# MYO_connector_2.net
KiCad netlist of a schematic drawn in EAGLE
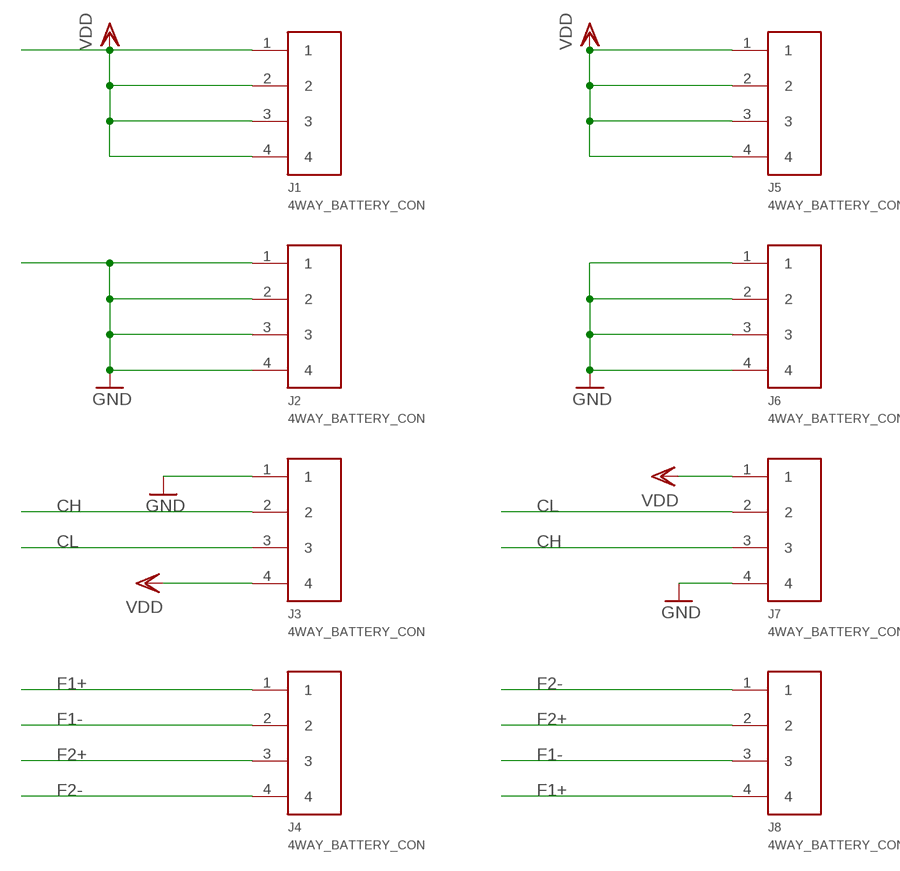
[diagram p0: schematic, sheet 1]

(export (version "E")
  (design (tool "Eeschema 10.0.6"))
  (components
    (comp (ref "J1")
      (value "4WAY_BATTERY_CON")
      (footprint "eagle-import:4-WAY-BATTERY_CON")
      (libsource (lib "eagle-import") (part "4WAY_BATTERY_CON"))
    )
    (comp (ref "J2")
      (value "4WAY_BATTERY_CON")
      (footprint "eagle-import:4-WAY-BATTERY_CON")
      (libsource (lib "eagle-import") (part "4WAY_BATTERY_CON"))
    )
    (comp (ref "J3")
      (value "4WAY_BATTERY_CON")
      (footprint "eagle-import:4-WAY-BATTERY_CON")
      (libsource (lib "eagle-import") (part "4WAY_BATTERY_CON"))
    )
    (comp (ref "J4")
      (value "4WAY_BATTERY_CON")
      (footprint "eagle-import:4-WAY-BATTERY_CON")
      (libsource (lib "eagle-import") (part "4WAY_BATTERY_CON"))
    )
    (comp (ref "J5")
      (value "4WAY_BATTERY_CON")
      (footprint "eagle-import:4-WAY-BATTERY_CON")
      (libsource (lib "eagle-import") (part "4WAY_BATTERY_CON"))
    )
    (comp (ref "J6")
      (value "4WAY_BATTERY_CON")
      (footprint "eagle-import:4-WAY-BATTERY_CON")
      (libsource (lib "eagle-import") (part "4WAY_BATTERY_CON"))
    )
    (comp (ref "J7")
      (value "4WAY_BATTERY_CON")
      (footprint "eagle-import:4-WAY-BATTERY_CON")
      (libsource (lib "eagle-import") (part "4WAY_BATTERY_CON"))
    )
    (comp (ref "J8")
      (value "4WAY_BATTERY_CON")
      (footprint "eagle-import:4-WAY-BATTERY_CON")
      (libsource (lib "eagle-import") (part "4WAY_BATTERY_CON"))
    )
  )
  (nets
    (net (code "1") (name "/CH") (class "Default")
      (node (ref "J3") (pin "2") (pinfunction "2_2") (pintype "bidirectional"))
      (node (ref "J7") (pin "3") (pinfunction "3_3") (pintype "bidirectional"))
    )
    (net (code "2") (name "/CL") (class "Default")
      (node (ref "J3") (pin "3") (pinfunction "3_3") (pintype "bidirectional"))
      (node (ref "J7") (pin "2") (pinfunction "2_2") (pintype "bidirectional"))
    )
    (net (code "3") (name "/F1+") (class "Default")
      (node (ref "J4") (pin "1") (pinfunction "1_1") (pintype "bidirectional"))
      (node (ref "J8") (pin "4") (pinfunction "4_4") (pintype "bidirectional"))
    )
    (net (code "4") (name "/F1-") (class "Default")
      (node (ref "J4") (pin "2") (pinfunction "2_2") (pintype "bidirectional"))
      (node (ref "J8") (pin "3") (pinfunction "3_3") (pintype "bidirectional"))
    )
    (net (code "5") (name "/F2+") (class "Default")
      (node (ref "J4") (pin "3") (pinfunction "3_3") (pintype "bidirectional"))
      (node (ref "J8") (pin "2") (pinfunction "2_2") (pintype "bidirectional"))
    )
    (net (code "6") (name "/F2-") (class "Default")
      (node (ref "J4") (pin "4") (pinfunction "4_4") (pintype "bidirectional"))
      (node (ref "J8") (pin "1") (pinfunction "1_1") (pintype "bidirectional"))
    )
    (net (code "7") (name "GND") (class "Default")
      (node (ref "J2") (pin "1") (pinfunction "1_1") (pintype "bidirectional"))
      (node (ref "J2") (pin "2") (pinfunction "2_2") (pintype "bidirectional"))
      (node (ref "J2") (pin "3") (pinfunction "3_3") (pintype "bidirectional"))
      (node (ref "J2") (pin "4") (pinfunction "4_4") (pintype "bidirectional"))
      (node (ref "J3") (pin "1") (pinfunction "1_1") (pintype "bidirectional"))
      (node (ref "J6") (pin "1") (pinfunction "1_1") (pintype "bidirectional"))
      (node (ref "J6") (pin "2") (pinfunction "2_2") (pintype "bidirectional"))
      (node (ref "J6") (pin "3") (pinfunction "3_3") (pintype "bidirectional"))
      (node (ref "J6") (pin "4") (pinfunction "4_4") (pintype "bidirectional"))
      (node (ref "J7") (pin "4") (pinfunction "4_4") (pintype "bidirectional"))
    )
    (net (code "8") (name "VDD") (class "Default")
      (node (ref "J1") (pin "1") (pinfunction "1_1") (pintype "bidirectional"))
      (node (ref "J1") (pin "2") (pinfunction "2_2") (pintype "bidirectional"))
      (node (ref "J1") (pin "3") (pinfunction "3_3") (pintype "bidirectional"))
      (node (ref "J1") (pin "4") (pinfunction "4_4") (pintype "bidirectional"))
      (node (ref "J3") (pin "4") (pinfunction "4_4") (pintype "bidirectional"))
      (node (ref "J5") (pin "1") (pinfunction "1_1") (pintype "bidirectional"))
      (node (ref "J5") (pin "2") (pinfunction "2_2") (pintype "bidirectional"))
      (node (ref "J5") (pin "3") (pinfunction "3_3") (pintype "bidirectional"))
      (node (ref "J5") (pin "4") (pinfunction "4_4") (pintype "bidirectional"))
      (node (ref "J7") (pin "1") (pinfunction "1_1") (pintype "bidirectional"))
    )
  )
)
